# Address_Termination.net
KiCad netlist of a schematic drawn in Altium Designer
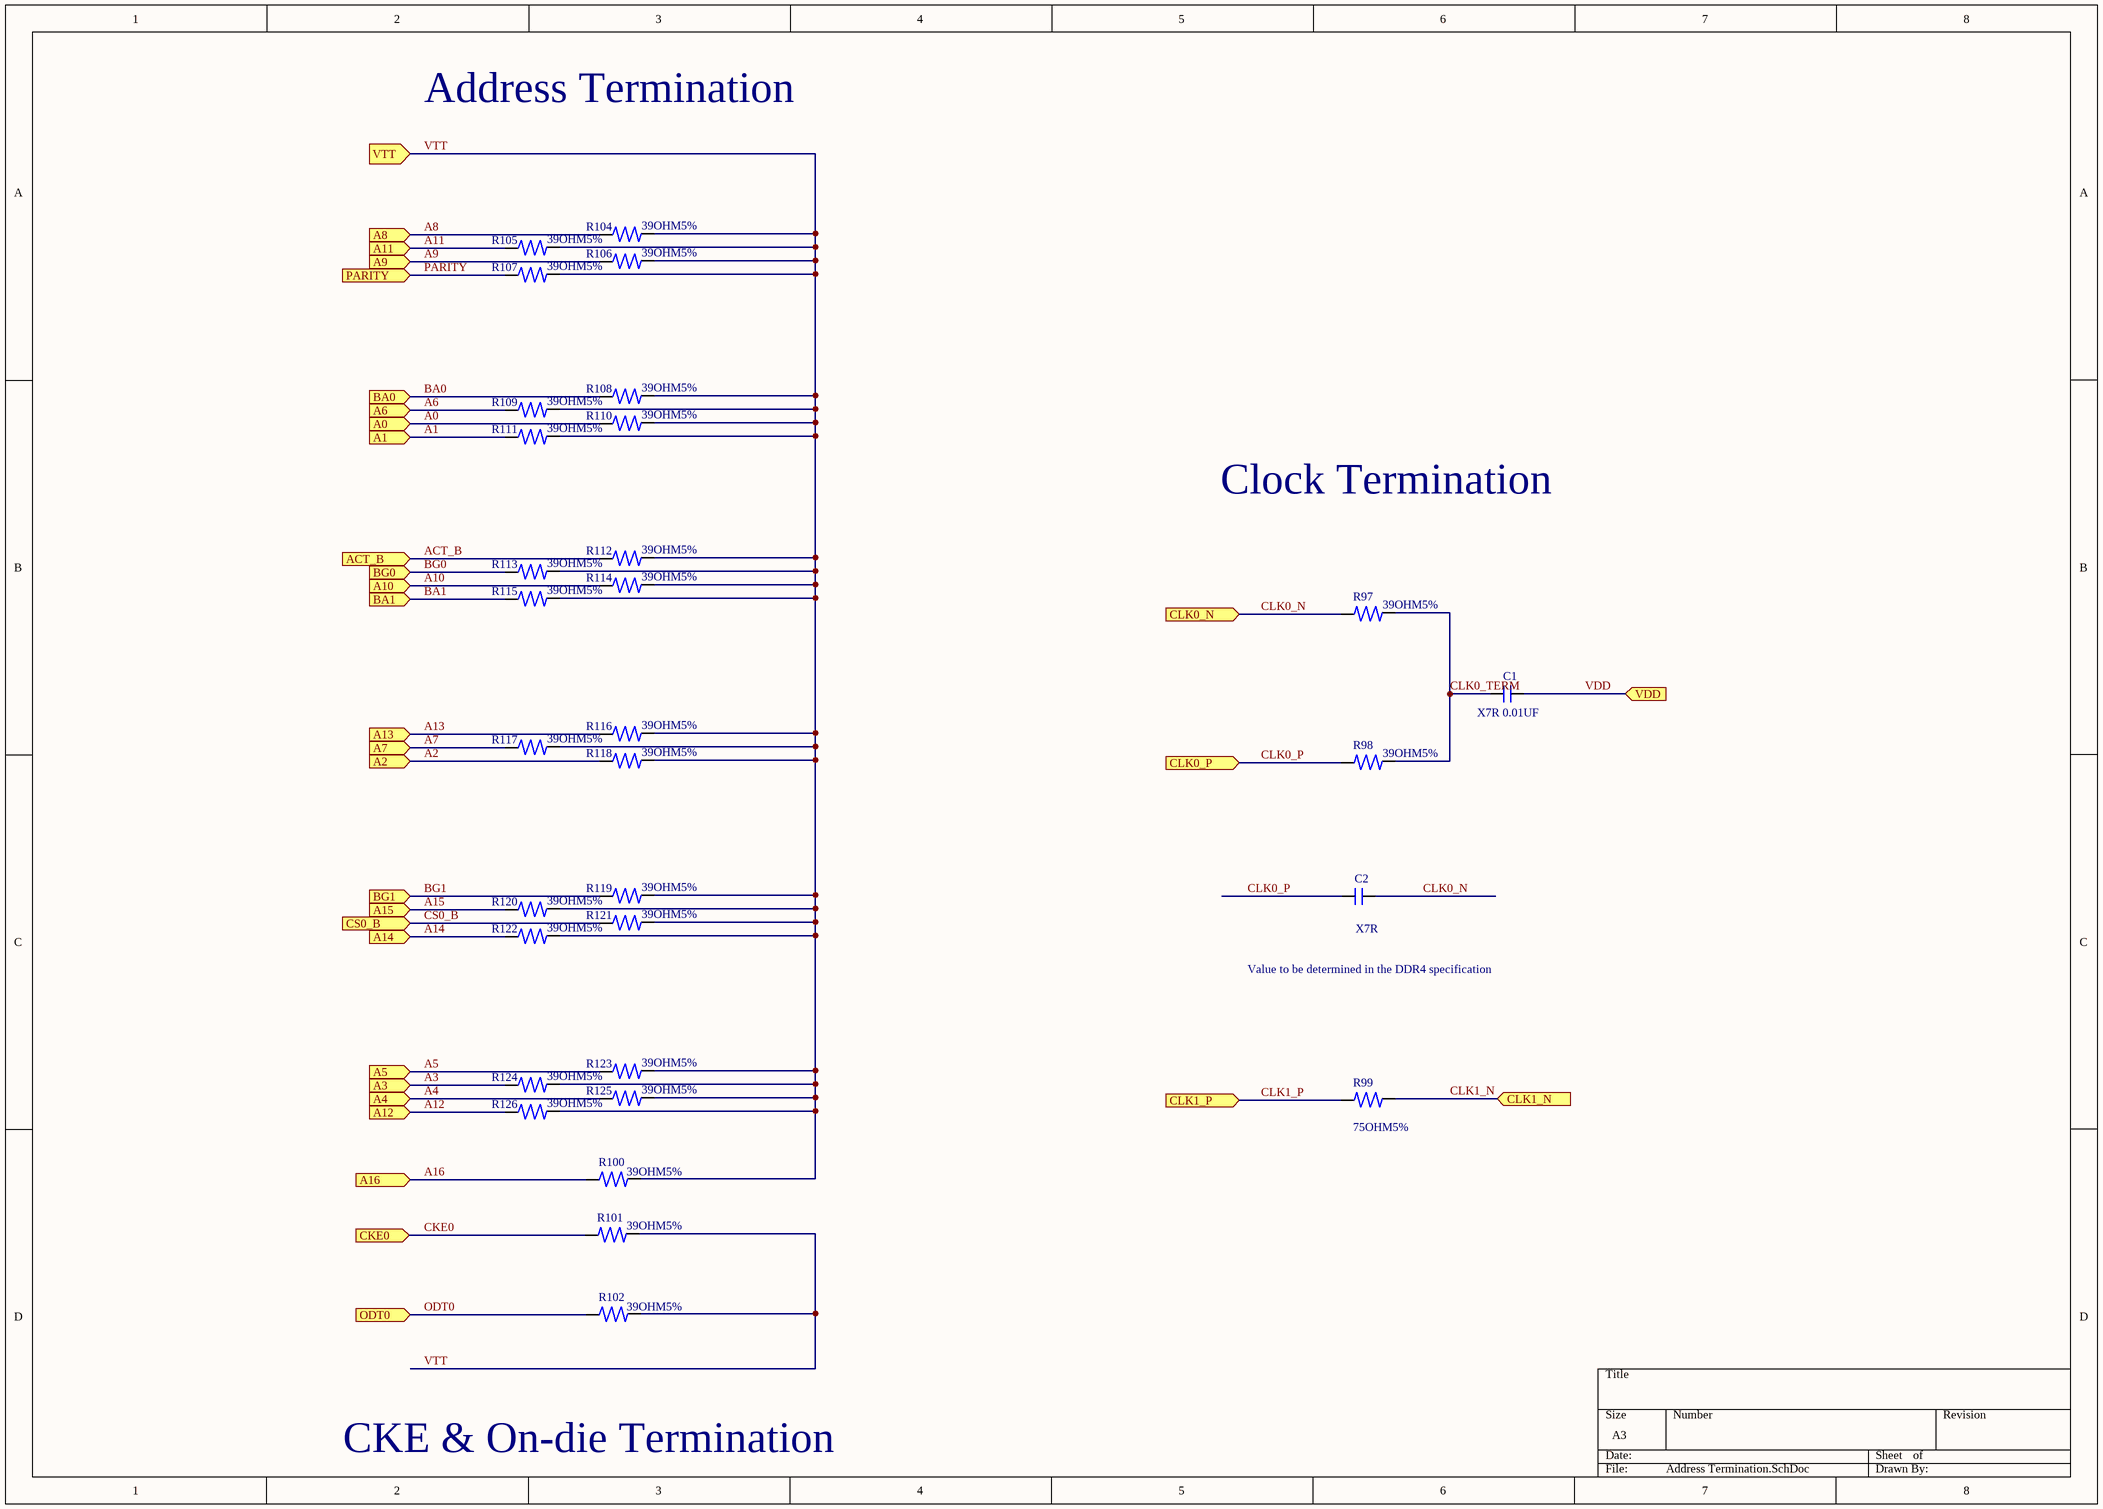
[diagram p0: Address Termination.SchDoc]

(export (version "E")
  (design (tool "Eeschema 10.0.6"))
  (components
    (comp (ref "C1")
      (value "Capacitor 0402")
      (footprint "Capacitor 0402")
      (fields
        (field (name "MANUFACTURER") "Vishay")
        (field (name "MANUFACTURER PART NUMBER") "CRCW060310K0FKEA")
        (field (name "TOLERANCE") "1%")
        (field (name "CAPACITANCE") "X7R 0.01UF")
      )
      (libsource (lib "RouterIntLib") (part "Capacitor 0201"))
    )
    (comp (ref "C2")
      (value "Capacitor 0402")
      (footprint "Capacitor 0402")
      (fields
        (field (name "MANUFACTURER") "Vishay")
        (field (name "MANUFACTURER PART NUMBER") "CRCW060310K0FKEA")
        (field (name "TOLERANCE") "1%")
        (field (name "CAPACITANCE") "X7R")
      )
      (libsource (lib "RouterIntLib") (part "Capacitor 0201"))
    )
    (comp (ref "R97")
      (value "Resistor 0402")
      (footprint "Resistor 0402")
      (fields
        (field (name "MANUFACTURER") "Vishay")
        (field (name "MANUFACTURER PART NUMBER") "CRCW060310K0FKEA")
        (field (name "TOLERANCE") "1%")
        (field (name "RESISTANCE") "39OHM5%")
      )
      (libsource (lib "RouterIntLib") (part "Resistor 0201"))
    )
    (comp (ref "R98")
      (value "Resistor 0402")
      (footprint "Resistor 0402")
      (fields
        (field (name "MANUFACTURER") "Vishay")
        (field (name "MANUFACTURER PART NUMBER") "CRCW060310K0FKEA")
        (field (name "TOLERANCE") "1%")
        (field (name "RESISTANCE") "39OHM5%")
      )
      (libsource (lib "RouterIntLib") (part "Resistor 0201"))
    )
    (comp (ref "R99")
      (value "Resistor 0402")
      (footprint "Resistor 0402")
      (fields
        (field (name "MANUFACTURER") "Vishay")
        (field (name "MANUFACTURER PART NUMBER") "CRCW060310K0FKEA")
        (field (name "TOLERANCE") "1%")
        (field (name "RESISTANCE") "75OHM5%")
      )
      (libsource (lib "RouterIntLib") (part "Resistor 0201"))
    )
    (comp (ref "R100")
      (value "Resistor 0402")
      (footprint "Resistor 0402")
      (fields
        (field (name "MANUFACTURER") "Vishay")
        (field (name "MANUFACTURER PART NUMBER") "CRCW060310K0FKEA")
        (field (name "TOLERANCE") "1%")
        (field (name "RESISTANCE") "39OHM5%")
      )
      (libsource (lib "RouterIntLib") (part "Resistor 0201"))
    )
    (comp (ref "R101")
      (value "Resistor 0402")
      (footprint "Resistor 0402")
      (fields
        (field (name "MANUFACTURER") "Vishay")
        (field (name "MANUFACTURER PART NUMBER") "CRCW060310K0FKEA")
        (field (name "TOLERANCE") "1%")
        (field (name "RESISTANCE") "39OHM5%")
      )
      (libsource (lib "RouterIntLib") (part "Resistor 0201"))
    )
    (comp (ref "R102")
      (value "Resistor 0402")
      (footprint "Resistor 0402")
      (fields
        (field (name "MANUFACTURER") "Vishay")
        (field (name "MANUFACTURER PART NUMBER") "CRCW060310K0FKEA")
        (field (name "TOLERANCE") "1%")
        (field (name "RESISTANCE") "39OHM5%")
      )
      (libsource (lib "RouterIntLib") (part "Resistor 0201"))
    )
    (comp (ref "R104")
      (value "Resistor 0402")
      (footprint "Resistor 0402")
      (fields
        (field (name "MANUFACTURER") "Vishay")
        (field (name "MANUFACTURER PART NUMBER") "CRCW060310K0FKEA")
        (field (name "TOLERANCE") "1%")
        (field (name "RESISTANCE") "39OHM5%")
      )
      (libsource (lib "RouterIntLib") (part "Resistor 0201"))
    )
    (comp (ref "R105")
      (value "Resistor 0402")
      (footprint "Resistor 0402")
      (fields
        (field (name "MANUFACTURER") "Vishay")
        (field (name "MANUFACTURER PART NUMBER") "CRCW060310K0FKEA")
        (field (name "TOLERANCE") "1%")
        (field (name "RESISTANCE") "39OHM5%")
      )
      (libsource (lib "RouterIntLib") (part "Resistor 0201"))
    )
    (comp (ref "R106")
      (value "Resistor 0402")
      (footprint "Resistor 0402")
      (fields
        (field (name "MANUFACTURER") "Vishay")
        (field (name "MANUFACTURER PART NUMBER") "CRCW060310K0FKEA")
        (field (name "TOLERANCE") "1%")
        (field (name "RESISTANCE") "39OHM5%")
      )
      (libsource (lib "RouterIntLib") (part "Resistor 0201"))
    )
    (comp (ref "R107")
      (value "Resistor 0402")
      (footprint "Resistor 0402")
      (fields
        (field (name "MANUFACTURER") "Vishay")
        (field (name "MANUFACTURER PART NUMBER") "CRCW060310K0FKEA")
        (field (name "TOLERANCE") "1%")
        (field (name "RESISTANCE") "39OHM5%")
      )
      (libsource (lib "RouterIntLib") (part "Resistor 0201"))
    )
    (comp (ref "R108")
      (value "Resistor 0402")
      (footprint "Resistor 0402")
      (fields
        (field (name "MANUFACTURER") "Vishay")
        (field (name "MANUFACTURER PART NUMBER") "CRCW060310K0FKEA")
        (field (name "TOLERANCE") "1%")
        (field (name "RESISTANCE") "39OHM5%")
      )
      (libsource (lib "RouterIntLib") (part "Resistor 0201"))
    )
    (comp (ref "R109")
      (value "Resistor 0402")
      (footprint "Resistor 0402")
      (fields
        (field (name "MANUFACTURER") "Vishay")
        (field (name "MANUFACTURER PART NUMBER") "CRCW060310K0FKEA")
        (field (name "TOLERANCE") "1%")
        (field (name "RESISTANCE") "39OHM5%")
      )
      (libsource (lib "RouterIntLib") (part "Resistor 0201"))
    )
    (comp (ref "R110")
      (value "Resistor 0402")
      (footprint "Resistor 0402")
      (fields
        (field (name "MANUFACTURER") "Vishay")
        (field (name "MANUFACTURER PART NUMBER") "CRCW060310K0FKEA")
        (field (name "TOLERANCE") "1%")
        (field (name "RESISTANCE") "39OHM5%")
      )
      (libsource (lib "RouterIntLib") (part "Resistor 0201"))
    )
    (comp (ref "R111")
      (value "Resistor 0402")
      (footprint "Resistor 0402")
      (fields
        (field (name "MANUFACTURER") "Vishay")
        (field (name "MANUFACTURER PART NUMBER") "CRCW060310K0FKEA")
        (field (name "TOLERANCE") "1%")
        (field (name "RESISTANCE") "39OHM5%")
      )
      (libsource (lib "RouterIntLib") (part "Resistor 0201"))
    )
    (comp (ref "R112")
      (value "Resistor 0402")
      (footprint "Resistor 0402")
      (fields
        (field (name "MANUFACTURER") "Vishay")
        (field (name "MANUFACTURER PART NUMBER") "CRCW060310K0FKEA")
        (field (name "TOLERANCE") "1%")
        (field (name "RESISTANCE") "39OHM5%")
      )
      (libsource (lib "RouterIntLib") (part "Resistor 0201"))
    )
    (comp (ref "R113")
      (value "Resistor 0402")
      (footprint "Resistor 0402")
      (fields
        (field (name "MANUFACTURER") "Vishay")
        (field (name "MANUFACTURER PART NUMBER") "CRCW060310K0FKEA")
        (field (name "TOLERANCE") "1%")
        (field (name "RESISTANCE") "39OHM5%")
      )
      (libsource (lib "RouterIntLib") (part "Resistor 0201"))
    )
    (comp (ref "R114")
      (value "Resistor 0402")
      (footprint "Resistor 0402")
      (fields
        (field (name "MANUFACTURER") "Vishay")
        (field (name "MANUFACTURER PART NUMBER") "CRCW060310K0FKEA")
        (field (name "TOLERANCE") "1%")
        (field (name "RESISTANCE") "39OHM5%")
      )
      (libsource (lib "RouterIntLib") (part "Resistor 0201"))
    )
    (comp (ref "R115")
      (value "Resistor 0402")
      (footprint "Resistor 0402")
      (fields
        (field (name "MANUFACTURER") "Vishay")
        (field (name "MANUFACTURER PART NUMBER") "CRCW060310K0FKEA")
        (field (name "TOLERANCE") "1%")
        (field (name "RESISTANCE") "39OHM5%")
      )
      (libsource (lib "RouterIntLib") (part "Resistor 0201"))
    )
    (comp (ref "R116")
      (value "Resistor 0402")
      (footprint "Resistor 0402")
      (fields
        (field (name "MANUFACTURER") "Vishay")
        (field (name "MANUFACTURER PART NUMBER") "CRCW060310K0FKEA")
        (field (name "TOLERANCE") "1%")
        (field (name "RESISTANCE") "39OHM5%")
      )
      (libsource (lib "RouterIntLib") (part "Resistor 0201"))
    )
    (comp (ref "R117")
      (value "Resistor 0402")
      (footprint "Resistor 0402")
      (fields
        (field (name "MANUFACTURER") "Vishay")
        (field (name "MANUFACTURER PART NUMBER") "CRCW060310K0FKEA")
        (field (name "TOLERANCE") "1%")
        (field (name "RESISTANCE") "39OHM5%")
      )
      (libsource (lib "RouterIntLib") (part "Resistor 0201"))
    )
    (comp (ref "R118")
      (value "Resistor 0402")
      (footprint "Resistor 0402")
      (fields
        (field (name "MANUFACTURER") "Vishay")
        (field (name "MANUFACTURER PART NUMBER") "CRCW060310K0FKEA")
        (field (name "TOLERANCE") "1%")
        (field (name "RESISTANCE") "39OHM5%")
      )
      (libsource (lib "RouterIntLib") (part "Resistor 0201"))
    )
    (comp (ref "R119")
      (value "Resistor 0402")
      (footprint "Resistor 0402")
      (fields
        (field (name "MANUFACTURER") "Vishay")
        (field (name "MANUFACTURER PART NUMBER") "CRCW060310K0FKEA")
        (field (name "TOLERANCE") "1%")
        (field (name "RESISTANCE") "39OHM5%")
      )
      (libsource (lib "RouterIntLib") (part "Resistor 0201"))
    )
    (comp (ref "R120")
      (value "Resistor 0402")
      (footprint "Resistor 0402")
      (fields
        (field (name "MANUFACTURER") "Vishay")
        (field (name "MANUFACTURER PART NUMBER") "CRCW060310K0FKEA")
        (field (name "TOLERANCE") "1%")
        (field (name "RESISTANCE") "39OHM5%")
      )
      (libsource (lib "RouterIntLib") (part "Resistor 0201"))
    )
    (comp (ref "R121")
      (value "Resistor 0402")
      (footprint "Resistor 0402")
      (fields
        (field (name "MANUFACTURER") "Vishay")
        (field (name "MANUFACTURER PART NUMBER") "CRCW060310K0FKEA")
        (field (name "TOLERANCE") "1%")
        (field (name "RESISTANCE") "39OHM5%")
      )
      (libsource (lib "RouterIntLib") (part "Resistor 0201"))
    )
    (comp (ref "R122")
      (value "Resistor 0402")
      (footprint "Resistor 0402")
      (fields
        (field (name "MANUFACTURER") "Vishay")
        (field (name "MANUFACTURER PART NUMBER") "CRCW060310K0FKEA")
        (field (name "TOLERANCE") "1%")
        (field (name "RESISTANCE") "39OHM5%")
      )
      (libsource (lib "RouterIntLib") (part "Resistor 0201"))
    )
    (comp (ref "R123")
      (value "Resistor 0402")
      (footprint "Resistor 0402")
      (fields
        (field (name "MANUFACTURER") "Vishay")
        (field (name "MANUFACTURER PART NUMBER") "CRCW060310K0FKEA")
        (field (name "TOLERANCE") "1%")
        (field (name "RESISTANCE") "39OHM5%")
      )
      (libsource (lib "RouterIntLib") (part "Resistor 0201"))
    )
    (comp (ref "R124")
      (value "Resistor 0402")
      (footprint "Resistor 0402")
      (fields
        (field (name "MANUFACTURER") "Vishay")
        (field (name "MANUFACTURER PART NUMBER") "CRCW060310K0FKEA")
        (field (name "TOLERANCE") "1%")
        (field (name "RESISTANCE") "39OHM5%")
      )
      (libsource (lib "RouterIntLib") (part "Resistor 0201"))
    )
    (comp (ref "R125")
      (value "Resistor 0402")
      (footprint "Resistor 0402")
      (fields
        (field (name "MANUFACTURER") "Vishay")
        (field (name "MANUFACTURER PART NUMBER") "CRCW060310K0FKEA")
        (field (name "TOLERANCE") "1%")
        (field (name "RESISTANCE") "39OHM5%")
      )
      (libsource (lib "RouterIntLib") (part "Resistor 0201"))
    )
    (comp (ref "R126")
      (value "Resistor 0402")
      (footprint "Resistor 0402")
      (fields
        (field (name "MANUFACTURER") "Vishay")
        (field (name "MANUFACTURER PART NUMBER") "CRCW060310K0FKEA")
        (field (name "TOLERANCE") "1%")
        (field (name "RESISTANCE") "39OHM5%")
      )
      (libsource (lib "RouterIntLib") (part "Resistor 0201"))
    )
  )
  (nets
    (net (code "1") (name "/A0") (class "Default")
      (node (ref "R110") (pin "1") (pinfunction "1_1") (pintype "passive"))
    )
    (net (code "2") (name "/A1") (class "Default")
      (node (ref "R111") (pin "1") (pinfunction "1_1") (pintype "passive"))
    )
    (net (code "3") (name "/A2") (class "Default")
      (node (ref "R118") (pin "1") (pinfunction "1_1") (pintype "passive"))
    )
    (net (code "4") (name "/A3") (class "Default")
      (node (ref "R124") (pin "1") (pinfunction "1_1") (pintype "passive"))
    )
    (net (code "5") (name "/A4") (class "Default")
      (node (ref "R125") (pin "1") (pinfunction "1_1") (pintype "passive"))
    )
    (net (code "6") (name "/A5") (class "Default")
      (node (ref "R123") (pin "1") (pinfunction "1_1") (pintype "passive"))
    )
    (net (code "7") (name "/A6") (class "Default")
      (node (ref "R109") (pin "1") (pinfunction "1_1") (pintype "passive"))
    )
    (net (code "8") (name "/A7") (class "Default")
      (node (ref "R117") (pin "1") (pinfunction "1_1") (pintype "passive"))
    )
    (net (code "9") (name "/A8") (class "Default")
      (node (ref "R104") (pin "1") (pinfunction "1_1") (pintype "passive"))
    )
    (net (code "10") (name "/A9") (class "Default")
      (node (ref "R106") (pin "1") (pinfunction "1_1") (pintype "passive"))
    )
    (net (code "11") (name "/A10") (class "Default")
      (node (ref "R114") (pin "1") (pinfunction "1_1") (pintype "passive"))
    )
    (net (code "12") (name "/A11") (class "Default")
      (node (ref "R105") (pin "1") (pinfunction "1_1") (pintype "passive"))
    )
    (net (code "13") (name "/A12") (class "Default")
      (node (ref "R126") (pin "1") (pinfunction "1_1") (pintype "passive"))
    )
    (net (code "14") (name "/A13") (class "Default")
      (node (ref "R116") (pin "1") (pinfunction "1_1") (pintype "passive"))
    )
    (net (code "15") (name "/A14") (class "Default")
      (node (ref "R122") (pin "1") (pinfunction "1_1") (pintype "passive"))
    )
    (net (code "16") (name "/A15") (class "Default")
      (node (ref "R120") (pin "1") (pinfunction "1_1") (pintype "passive"))
    )
    (net (code "17") (name "/A16") (class "Default")
      (node (ref "R100") (pin "1") (pinfunction "1_1") (pintype "passive"))
    )
    (net (code "18") (name "/ACT_B") (class "Default")
      (node (ref "R112") (pin "1") (pinfunction "1_1") (pintype "passive"))
    )
    (net (code "19") (name "/BA0") (class "Default")
      (node (ref "R108") (pin "1") (pinfunction "1_1") (pintype "passive"))
    )
    (net (code "20") (name "/BA1") (class "Default")
      (node (ref "R115") (pin "1") (pinfunction "1_1") (pintype "passive"))
    )
    (net (code "21") (name "/BG0") (class "Default")
      (node (ref "R113") (pin "1") (pinfunction "1_1") (pintype "passive"))
    )
    (net (code "22") (name "/BG1") (class "Default")
      (node (ref "R119") (pin "1") (pinfunction "1_1") (pintype "passive"))
    )
    (net (code "23") (name "/CKE0") (class "Default")
      (node (ref "R101") (pin "1") (pinfunction "1_1") (pintype "passive"))
    )
    (net (code "24") (name "/CLK0_N") (class "Default")
      (node (ref "C2") (pin "2") (pinfunction "2_2") (pintype "passive"))
      (node (ref "R97") (pin "1") (pinfunction "1_1") (pintype "passive"))
    )
    (net (code "25") (name "/CLK0_P") (class "Default")
      (node (ref "C2") (pin "1") (pinfunction "1_1") (pintype "passive"))
      (node (ref "R98") (pin "1") (pinfunction "1_1") (pintype "passive"))
    )
    (net (code "26") (name "/CLK0_TERM") (class "Default")
      (node (ref "C1") (pin "1") (pinfunction "1_1") (pintype "passive"))
      (node (ref "R97") (pin "2") (pinfunction "2_2") (pintype "passive"))
      (node (ref "R98") (pin "2") (pinfunction "2_2") (pintype "passive"))
    )
    (net (code "27") (name "/CLK1_N") (class "Default")
      (node (ref "R99") (pin "2") (pinfunction "2_2") (pintype "passive"))
    )
    (net (code "28") (name "/CLK1_P") (class "Default")
      (node (ref "R99") (pin "1") (pinfunction "1_1") (pintype "passive"))
    )
    (net (code "29") (name "/CS0_B") (class "Default")
      (node (ref "R121") (pin "1") (pinfunction "1_1") (pintype "passive"))
    )
    (net (code "30") (name "/ODT0") (class "Default")
      (node (ref "R102") (pin "1") (pinfunction "1_1") (pintype "passive"))
    )
    (net (code "31") (name "/PARITY") (class "Default")
      (node (ref "R107") (pin "1") (pinfunction "1_1") (pintype "passive"))
    )
    (net (code "32") (name "/VDD") (class "Default")
      (node (ref "C1") (pin "2") (pinfunction "2_2") (pintype "passive"))
    )
    (net (code "33") (name "/VTT") (class "Default")
      (node (ref "R100") (pin "2") (pinfunction "2_2") (pintype "passive"))
      (node (ref "R101") (pin "2") (pinfunction "2_2") (pintype "passive"))
      (node (ref "R102") (pin "2") (pinfunction "2_2") (pintype "passive"))
      (node (ref "R104") (pin "2") (pinfunction "2_2") (pintype "passive"))
      (node (ref "R105") (pin "2") (pinfunction "2_2") (pintype "passive"))
      (node (ref "R106") (pin "2") (pinfunction "2_2") (pintype "passive"))
      (node (ref "R107") (pin "2") (pinfunction "2_2") (pintype "passive"))
      (node (ref "R108") (pin "2") (pinfunction "2_2") (pintype "passive"))
      (node (ref "R109") (pin "2") (pinfunction "2_2") (pintype "passive"))
      (node (ref "R110") (pin "2") (pinfunction "2_2") (pintype "passive"))
      (node (ref "R111") (pin "2") (pinfunction "2_2") (pintype "passive"))
      (node (ref "R112") (pin "2") (pinfunction "2_2") (pintype "passive"))
      (node (ref "R113") (pin "2") (pinfunction "2_2") (pintype "passive"))
      (node (ref "R114") (pin "2") (pinfunction "2_2") (pintype "passive"))
      (node (ref "R115") (pin "2") (pinfunction "2_2") (pintype "passive"))
      (node (ref "R116") (pin "2") (pinfunction "2_2") (pintype "passive"))
      (node (ref "R117") (pin "2") (pinfunction "2_2") (pintype "passive"))
      (node (ref "R118") (pin "2") (pinfunction "2_2") (pintype "passive"))
      (node (ref "R119") (pin "2") (pinfunction "2_2") (pintype "passive"))
      (node (ref "R120") (pin "2") (pinfunction "2_2") (pintype "passive"))
      (node (ref "R121") (pin "2") (pinfunction "2_2") (pintype "passive"))
      (node (ref "R122") (pin "2") (pinfunction "2_2") (pintype "passive"))
      (node (ref "R123") (pin "2") (pinfunction "2_2") (pintype "passive"))
      (node (ref "R124") (pin "2") (pinfunction "2_2") (pintype "passive"))
      (node (ref "R125") (pin "2") (pinfunction "2_2") (pintype "passive"))
      (node (ref "R126") (pin "2") (pinfunction "2_2") (pintype "passive"))
    )
  )
)
